# VoltageRegulator.net
KiCad netlist of a schematic drawn in Altium Designer
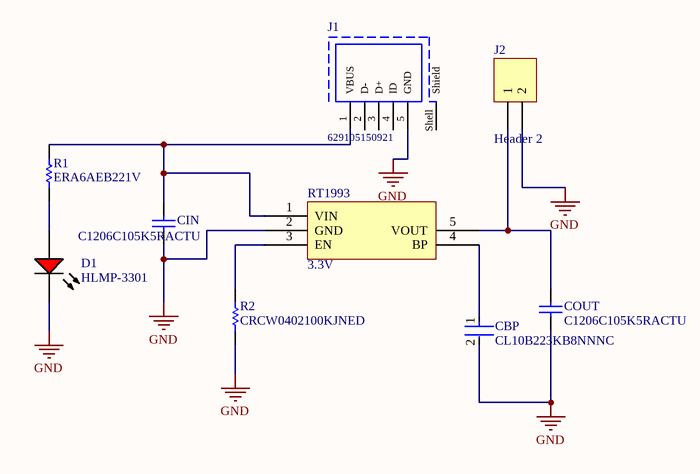
[diagram p0: VoltageRegulator.SchDoc]

(export (version "E")
  (design (tool "Eeschema 10.0.6"))
  (components
    (comp (ref "CBP")
      (value "CL10B223KB8NNNC")
      (footprint "FP-CL10-IPC_C")
      (description "Cap Ceramic 22nF 50V X7R ±10% Pad SMD 0603 +125°C T/R")
      (fields (field (name "VOLTAGE") "50V") (field (name "TOLERANCE") "10%"))
      (libsource (lib "Altium Content Vault") (part "b4654b650e69147ec39a6b967a45e02"))
    )
    (comp (ref "CIN")
      (value "C1206C105K5RACTU")
      (footprint "CAPC3216X110X50LL20T25")
      (description "Chip Capacitor, 1 uF, +/- 10%, 50 V, -55 to 125 degC, 1206 (3216 Metric), RoHS, Tape and Reel")
      (fields (field (name "MANUFACTURER") "Kemet") (field (name "TOLERANCE") "10%"))
      (libsource (lib "Altium Content Vault") (part "CAP-NP-2"))
    )
    (comp (ref "COUT")
      (value "C1206C105K5RACTU")
      (footprint "CAPC3216X110X50LL20T25")
      (description "Chip Capacitor, 1 uF, +/- 10%, 50 V, -55 to 125 degC, 1206 (3216 Metric), RoHS, Tape and Reel")
      (fields (field (name "MANUFACTURER") "Kemet") (field (name "TOLERANCE") "10%"))
      (libsource (lib "Altium Content Vault") (part "CAP-NP-2"))
    )
    (comp (ref "D1")
      (value "HLMP-3301")
      (footprint "AVAG-HLMP-3301-2")
      (description "T-1 3/4 (5 mm) Diffused LED Lamp, 1.9 V, -40 to 100 degC, 2-Pin THD, RoHS, Bulk")
      (fields (field (name "MANUFACTURER") "Avago"))
      (libsource (lib "Altium Content Vault") (part "LED-RED-K1A2-2"))
    )
    (comp (ref "J1")
      (value "629105150921")
      (footprint "629105150921")
      (description "Micro USB 2.0 Type AB Receptacle WR-COM, Horizontal, SMT")
      (fields (field (name "MANUFACTURER") "Wurth Elektronik") (field (name "PUBLISHER") "WurthElektronik"))
      (libsource (lib "Altium Content Vault") (part "WE-USB-5-1SHLD"))
    )
    (comp (ref "J2")
      (value "Header 2")
      (footprint "HDR1X2")
      (description "Header, 2-Pin")
      (fields (field (name "PUBLISHER") "Altium Limited"))
      (libsource (lib "Miscellaneous Connectors") (part "Header 2"))
    )
    (comp (ref "R1")
      (value "ERA6AEB221V")
      (footprint "RESC2013X60X40NL20T25")
      (fields (field (name "MANUFACTURER") "Panasonic"))
      (libsource (lib "Altium Content Vault") (part "RES"))
    )
    (comp (ref "R2")
      (value "CRCW0402100KJNED")
      (footprint "RESC1005X40X25LL05T05")
      (fields (field (name "MANUFACTURER") "Vishay Dale"))
      (libsource (lib "Altium Content Vault") (part "RES"))
    )
    (comp (ref "RT1993")
      (value "3.3V")
      (footprint "SOT85P279X130-5N")
      (description "IC REG LINEAR 3.3V 300MA SOT23-5")
      (libsource (lib "RT1993-33GB") (part "KXEC-629051"))
    )
  )
  (nets
    (net (code "1") (name "GND") (class "Default")
      (node (ref "CBP") (pin "2") (pinfunction "2_2") (pintype "passive"))
      (node (ref "CIN") (pin "1") (pinfunction "1_1") (pintype "passive"))
      (node (ref "COUT") (pin "1") (pinfunction "1_1") (pintype "passive"))
      (node (ref "D1") (pin "1") (pinfunction "K_1") (pintype "passive"))
      (node (ref "J1") (pin "5") (pinfunction "GND_5") (pintype "passive"))
      (node (ref "J2") (pin "2") (pinfunction "2_2") (pintype "passive"))
      (node (ref "R2") (pin "1") (pinfunction "1_1") (pintype "passive"))
      (node (ref "RT1993") (pin "2") (pinfunction "GND_2") (pintype "power_in"))
    )
    (net (code "2") (name "Net-(D1-A)") (class "Default")
      (node (ref "D1") (pin "2") (pinfunction "A_2") (pintype "passive"))
      (node (ref "R1") (pin "1") (pinfunction "1_1") (pintype "passive"))
    )
    (net (code "3") (name "Net-(J1-VBUS)") (class "Default")
      (node (ref "CIN") (pin "2") (pinfunction "2_2") (pintype "passive"))
      (node (ref "J1") (pin "1") (pinfunction "VBUS_1") (pintype "passive"))
      (node (ref "R1") (pin "2") (pinfunction "2_2") (pintype "passive"))
      (node (ref "RT1993") (pin "1") (pinfunction "VIN_1") (pintype "power_in"))
    )
    (net (code "4") (name "Net-(RT1993-BP)") (class "Default")
      (node (ref "CBP") (pin "1") (pinfunction "1_1") (pintype "passive"))
      (node (ref "RT1993") (pin "4") (pinfunction "BP_4") (pintype "power_in"))
    )
    (net (code "5") (name "Net-(RT1993-EN)") (class "Default")
      (node (ref "R2") (pin "2") (pinfunction "2_2") (pintype "passive"))
      (node (ref "RT1993") (pin "3") (pinfunction "EN_3") (pintype "power_in"))
    )
    (net (code "6") (name "Net-(RT1993-VOUT)") (class "Default")
      (node (ref "COUT") (pin "2") (pinfunction "2_2") (pintype "passive"))
      (node (ref "J2") (pin "1") (pinfunction "1_1") (pintype "passive"))
      (node (ref "RT1993") (pin "5") (pinfunction "VOUT_5") (pintype "power_in"))
    )
    (net (code "7") (name "unconnected-(J1-D+-Pad3)") (class "Default")
      (node (ref "J1") (pin "3") (pinfunction "D+_3") (pintype "passive"))
    )
    (net (code "8") (name "unconnected-(J1-D--Pad2)") (class "Default")
      (node (ref "J1") (pin "2") (pinfunction "D-_2") (pintype "passive"))
    )
    (net (code "9") (name "unconnected-(J1-ID-Pad4)") (class "Default")
      (node (ref "J1") (pin "4") (pinfunction "ID_4") (pintype "passive"))
    )
    (net (code "10") (name "unconnected-(J1-Shield-PadShell)") (class "Default")
      (node (ref "J1") (pin "Shell") (pinfunction "Shield_Shell") (pintype "passive"))
    )
  )
)
